# Xbee_Shield_v11.net
KiCad netlist of a schematic drawn in EAGLE
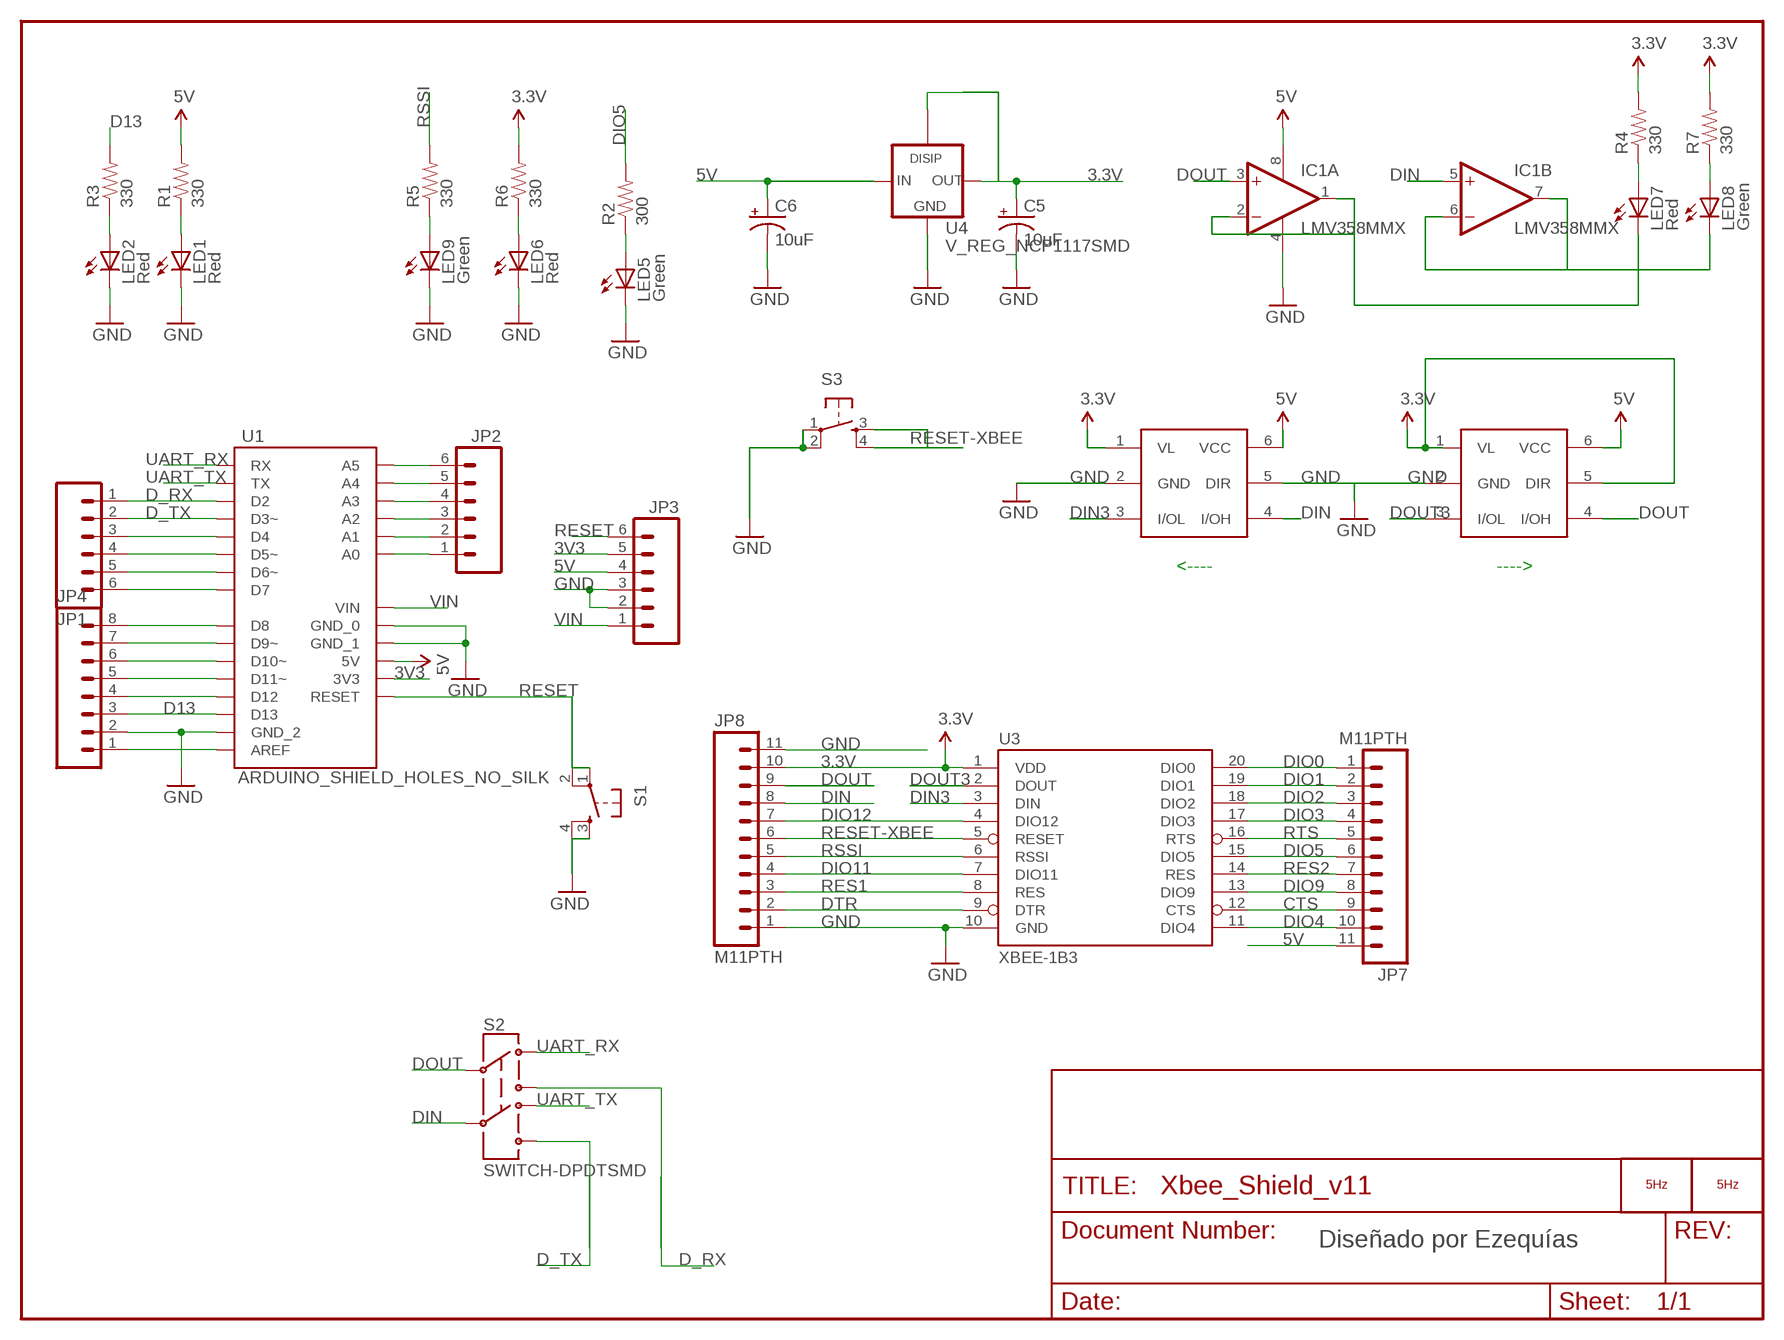
[diagram p0: schematic, sheet 1]

(export (version "E")
  (design (tool "Eeschema 10.0.6"))
  (components
    (comp (ref "C5")
      (value "10uF")
      (footprint "eagle-import:EIA3216")
      (libsource (lib "eagle-import") (part "CAP_POL1206"))
    )
    (comp (ref "C6")
      (value "10uF")
      (footprint "eagle-import:EIA3216")
      (libsource (lib "eagle-import") (part "CAP_POL1206"))
    )
    (comp (ref "IC1")
      (value "LMV358MMX")
      (footprint "eagle-import:MSOP08")
      (libsource (lib "eagle-import") (part "LMV358?MMX"))
    )
    (comp (ref "JP1")
      (value "M06SIP")
      (footprint "eagle-import:1X06")
      (libsource (lib "eagle-import") (part "M06SIP"))
    )
    (comp (ref "JP2")
      (value "M06SIP")
      (footprint "eagle-import:1X06")
      (libsource (lib "eagle-import") (part "M06SIP"))
    )
    (comp (ref "JP3")
      (value "M06SIP")
      (footprint "eagle-import:1X06")
      (libsource (lib "eagle-import") (part "M06SIP"))
    )
    (comp (ref "JP4")
      (value "M081X08")
      (footprint "eagle-import:1X08")
      (libsource (lib "eagle-import") (part "M081X08"))
    )
    (comp (ref "JP7")
      (value "M11PTH")
      (footprint "eagle-import:1X11")
      (libsource (lib "eagle-import") (part "M11PTH"))
    )
    (comp (ref "JP8")
      (value "M11PTH")
      (footprint "eagle-import:1X11")
      (libsource (lib "eagle-import") (part "M11PTH"))
    )
    (comp (ref "LED1")
      (value "Red")
      (footprint "eagle-import:LED-0603")
      (libsource (lib "eagle-import") (part "LED0603"))
    )
    (comp (ref "LED2")
      (value "Red")
      (footprint "eagle-import:LED-0603")
      (libsource (lib "eagle-import") (part "LED0603"))
    )
    (comp (ref "LED5")
      (value "Green")
      (footprint "eagle-import:LED-0603")
      (libsource (lib "eagle-import") (part "LED0603"))
    )
    (comp (ref "LED6")
      (value "Red")
      (footprint "eagle-import:LED-0603")
      (libsource (lib "eagle-import") (part "LED0603"))
    )
    (comp (ref "LED7")
      (value "Red")
      (footprint "eagle-import:LED-0603")
      (libsource (lib "eagle-import") (part "LED0603"))
    )
    (comp (ref "LED8")
      (value "Green")
      (footprint "eagle-import:LED-0603")
      (libsource (lib "eagle-import") (part "LED0603"))
    )
    (comp (ref "LED9")
      (value "Green")
      (footprint "eagle-import:LED-0603")
      (libsource (lib "eagle-import") (part "LED0603"))
    )
    (comp (ref "LOGO1")
      (value "LOGO_5HZ_H_20MM")
      (footprint "eagle-import:5HZ_LOGO_H_20MM")
      (libsource (lib "eagle-import") (part "LOGO_5HZ_H_20MM"))
    )
    (comp (ref "LOGO2")
      (value "LOGO_5HZ_WEB_COOPER_10MM")
      (footprint "eagle-import:5HZ_WEB_COOPER_10MM")
      (libsource (lib "eagle-import") (part "LOGO_5HZ_WEB_COOPER_10MM"))
    )
    (comp (ref "R1")
      (value "330")
      (footprint "eagle-import:0603-RES")
      (libsource (lib "eagle-import") (part "RESISTOR0603-RES"))
    )
    (comp (ref "R2")
      (value "300")
      (footprint "eagle-import:0603-RES")
      (libsource (lib "eagle-import") (part "RESISTOR0603-RES"))
    )
    (comp (ref "R3")
      (value "330")
      (footprint "eagle-import:0603-RES")
      (libsource (lib "eagle-import") (part "RESISTOR0603-RES"))
    )
    (comp (ref "R4")
      (value "330")
      (footprint "eagle-import:0603-RES")
      (libsource (lib "eagle-import") (part "RESISTOR0603-RES"))
    )
    (comp (ref "R5")
      (value "330")
      (footprint "eagle-import:0603-RES")
      (libsource (lib "eagle-import") (part "RESISTOR0603-RES"))
    )
    (comp (ref "R6")
      (value "330")
      (footprint "eagle-import:0603-RES")
      (libsource (lib "eagle-import") (part "RESISTOR0603-RES"))
    )
    (comp (ref "R7")
      (value "330")
      (footprint "eagle-import:0603-RES")
      (libsource (lib "eagle-import") (part "RESISTOR0603-RES"))
    )
    (comp (ref "S1")
      (value "TAC_SWITCHSMD")
      (footprint "eagle-import:TACTILE_SWITCH_SMD")
      (libsource (lib "eagle-import") (part "TAC_SWITCHSMD"))
    )
    (comp (ref "S2")
      (value "SWITCH-DPDTSMD")
      (footprint "eagle-import:AYZ0202")
      (libsource (lib "eagle-import") (part "SWITCH-DPDTSMD"))
    )
    (comp (ref "S3")
      (value "TAC_SWITCHSMD")
      (footprint "eagle-import:TACTILE_SWITCH_SMD")
      (libsource (lib "eagle-import") (part "TAC_SWITCHSMD"))
    )
    (comp (ref "U$7")
      (value "MAX337")
      (footprint "eagle-import:SOT-363")
      (libsource (lib "eagle-import") (part "MAX337"))
    )
    (comp (ref "U$8")
      (value "MAX337")
      (footprint "eagle-import:SOT-363")
      (libsource (lib "eagle-import") (part "MAX337"))
    )
    (comp (ref "U1")
      (value "ARDUINO_SHIELD_HOLES_NO_SILK")
      (footprint "eagle-import:UNO_SHIELD_HOLES_NO_SILK")
      (libsource (lib "eagle-import") (part "ARDUINO_SHIELD_HOLES_NO_SILK"))
    )
    (comp (ref "U3")
      (value "XBEE-1B3")
      (footprint "eagle-import:XBEE-SMD")
      (libsource (lib "eagle-import") (part "XBEE-1B3"))
    )
    (comp (ref "U4")
      (value "V_REG_NCP1117SMD")
      (footprint "eagle-import:SOT223")
      (libsource (lib "eagle-import") (part "V_REG_NCP1117SMD"))
    )
  )
  (nets
    (net (code "1") (name "/3V3") (class "Default")
      (node (ref "JP3") (pin "5") (pinfunction "5_5") (pintype "passive"))
      (node (ref "U1") (pin "3.3V") (pinfunction "3V3_3.3V") (pintype "bidirectional"))
    )
    (net (code "2") (name "/CTS") (class "Default")
      (node (ref "JP7") (pin "9") (pinfunction "9_9") (pintype "passive"))
      (node (ref "U3") (pin "12") (pinfunction "CTS_12") (pintype "output"))
    )
    (net (code "3") (name "/D13") (class "Default")
      (node (ref "JP4") (pin "3") (pinfunction "3_3") (pintype "passive"))
      (node (ref "R3") (pin "2") (pinfunction "2_2") (pintype "passive"))
      (node (ref "U1") (pin "D13") (pinfunction "D13_D13") (pintype "bidirectional"))
    )
    (net (code "4") (name "/DIN") (class "Default")
      (node (ref "IC1") (pin "5") (pinfunction "+IN_5") (pintype "input"))
      (node (ref "JP8") (pin "8") (pinfunction "8_8") (pintype "passive"))
      (node (ref "S2") (pin "5") (pinfunction "5_5") (pintype "bidirectional"))
      (node (ref "U$7") (pin "4") (pinfunction "I/OH_4") (pintype "bidirectional"))
    )
    (net (code "5") (name "/DIN3") (class "Default")
      (node (ref "U$7") (pin "3") (pinfunction "I/OL_3") (pintype "bidirectional"))
      (node (ref "U3") (pin "3") (pinfunction "DIN_3") (pintype "input"))
    )
    (net (code "6") (name "/DIO0") (class "Default")
      (node (ref "JP7") (pin "1") (pinfunction "1_1") (pintype "passive"))
      (node (ref "U3") (pin "20") (pinfunction "DIO0_20") (pintype "bidirectional"))
    )
    (net (code "7") (name "/DIO1") (class "Default")
      (node (ref "JP7") (pin "2") (pinfunction "2_2") (pintype "passive"))
      (node (ref "U3") (pin "19") (pinfunction "DIO1_19") (pintype "bidirectional"))
    )
    (net (code "8") (name "/DIO2") (class "Default")
      (node (ref "JP7") (pin "3") (pinfunction "3_3") (pintype "passive"))
      (node (ref "U3") (pin "18") (pinfunction "DIO2_18") (pintype "bidirectional"))
    )
    (net (code "9") (name "/DIO3") (class "Default")
      (node (ref "JP7") (pin "4") (pinfunction "4_4") (pintype "passive"))
      (node (ref "U3") (pin "17") (pinfunction "DIO3_17") (pintype "bidirectional"))
    )
    (net (code "10") (name "/DIO4") (class "Default")
      (node (ref "JP7") (pin "10") (pinfunction "10_10") (pintype "passive"))
      (node (ref "U3") (pin "11") (pinfunction "DIO4_11") (pintype "bidirectional"))
    )
    (net (code "11") (name "/DIO5") (class "Default")
      (node (ref "JP7") (pin "6") (pinfunction "6_6") (pintype "passive"))
      (node (ref "R2") (pin "2") (pinfunction "2_2") (pintype "passive"))
      (node (ref "U3") (pin "15") (pinfunction "DIO5_15") (pintype "bidirectional"))
    )
    (net (code "12") (name "/DIO9") (class "Default")
      (node (ref "JP7") (pin "8") (pinfunction "8_8") (pintype "passive"))
      (node (ref "U3") (pin "13") (pinfunction "DIO9_13") (pintype "bidirectional"))
    )
    (net (code "13") (name "/DIO11") (class "Default")
      (node (ref "JP8") (pin "4") (pinfunction "4_4") (pintype "passive"))
      (node (ref "U3") (pin "7") (pinfunction "DIO11_7") (pintype "bidirectional"))
    )
    (net (code "14") (name "/DIO12") (class "Default")
      (node (ref "JP8") (pin "7") (pinfunction "7_7") (pintype "passive"))
      (node (ref "U3") (pin "4") (pinfunction "DIO12_4") (pintype "bidirectional"))
    )
    (net (code "15") (name "/DOUT") (class "Default")
      (node (ref "IC1") (pin "3") (pinfunction "+IN_3") (pintype "input"))
      (node (ref "JP8") (pin "9") (pinfunction "9_9") (pintype "passive"))
      (node (ref "S2") (pin "2") (pinfunction "2_2") (pintype "bidirectional"))
      (node (ref "U$8") (pin "4") (pinfunction "I/OH_4") (pintype "bidirectional"))
    )
    (net (code "16") (name "/DOUT3") (class "Default")
      (node (ref "U$8") (pin "3") (pinfunction "I/OL_3") (pintype "bidirectional"))
      (node (ref "U3") (pin "2") (pinfunction "DOUT_2") (pintype "output"))
    )
    (net (code "17") (name "/DTR") (class "Default")
      (node (ref "JP8") (pin "2") (pinfunction "2_2") (pintype "passive"))
      (node (ref "U3") (pin "9") (pinfunction "DTR_9") (pintype "bidirectional"))
    )
    (net (code "18") (name "/D_RX") (class "Default")
      (node (ref "JP1") (pin "1") (pinfunction "1_1") (pintype "passive"))
      (node (ref "S2") (pin "3") (pinfunction "3_3") (pintype "bidirectional"))
      (node (ref "U1") (pin "D2") (pinfunction "D2_D2") (pintype "bidirectional"))
    )
    (net (code "19") (name "/D_TX") (class "Default")
      (node (ref "JP1") (pin "2") (pinfunction "2_2") (pintype "passive"))
      (node (ref "S2") (pin "6") (pinfunction "6_6") (pintype "bidirectional"))
      (node (ref "U1") (pin "D3") (pinfunction "D3~{}_D3") (pintype "bidirectional"))
    )
    (net (code "20") (name "/RES1") (class "Default")
      (node (ref "JP8") (pin "3") (pinfunction "3_3") (pintype "passive"))
      (node (ref "U3") (pin "8") (pinfunction "RES_8") (pintype "bidirectional"))
    )
    (net (code "21") (name "/RES2") (class "Default")
      (node (ref "JP7") (pin "7") (pinfunction "7_7") (pintype "passive"))
      (node (ref "U3") (pin "14") (pinfunction "RES_14") (pintype "bidirectional"))
    )
    (net (code "22") (name "/RESET") (class "Default")
      (node (ref "JP3") (pin "6") (pinfunction "6_6") (pintype "passive"))
      (node (ref "S1") (pin "1") (pinfunction "1_1") (pintype "passive"))
      (node (ref "S1") (pin "2") (pinfunction "2_2") (pintype "passive"))
      (node (ref "U1") (pin "RES") (pinfunction "RESET_RES") (pintype "bidirectional"))
    )
    (net (code "23") (name "/RESET-XBEE") (class "Default")
      (node (ref "JP8") (pin "6") (pinfunction "6_6") (pintype "passive"))
      (node (ref "S3") (pin "3") (pinfunction "3_3") (pintype "passive"))
      (node (ref "S3") (pin "4") (pinfunction "4_4") (pintype "passive"))
      (node (ref "U3") (pin "5") (pinfunction "RESET_5") (pintype "input"))
    )
    (net (code "24") (name "/RSSI") (class "Default")
      (node (ref "JP8") (pin "5") (pinfunction "5_5") (pintype "passive"))
      (node (ref "R5") (pin "2") (pinfunction "2_2") (pintype "passive"))
      (node (ref "U3") (pin "6") (pinfunction "RSSI_6") (pintype "bidirectional"))
    )
    (net (code "25") (name "/RTS") (class "Default")
      (node (ref "JP7") (pin "5") (pinfunction "5_5") (pintype "passive"))
      (node (ref "U3") (pin "16") (pinfunction "RTS_16") (pintype "input"))
    )
    (net (code "26") (name "/UART_RX") (class "Default")
      (node (ref "S2") (pin "1") (pinfunction "1_1") (pintype "bidirectional"))
      (node (ref "U1") (pin "RX") (pinfunction "RX_RX") (pintype "bidirectional"))
    )
    (net (code "27") (name "/UART_TX") (class "Default")
      (node (ref "S2") (pin "4") (pinfunction "4_4") (pintype "bidirectional"))
      (node (ref "U1") (pin "TX") (pinfunction "TX_TX") (pintype "bidirectional"))
    )
    (net (code "28") (name "/VIN") (class "Default")
      (node (ref "JP3") (pin "1") (pinfunction "1_1") (pintype "passive"))
      (node (ref "U1") (pin "VIN") (pinfunction "VIN_VIN") (pintype "bidirectional"))
    )
    (net (code "29") (name "3.3V") (class "Default")
      (node (ref "C5") (pin "A") (pinfunction "+_A") (pintype "passive"))
      (node (ref "JP8") (pin "10") (pinfunction "10_10") (pintype "passive"))
      (node (ref "R4") (pin "2") (pinfunction "2_2") (pintype "passive"))
      (node (ref "R6") (pin "2") (pinfunction "2_2") (pintype "passive"))
      (node (ref "R7") (pin "2") (pinfunction "2_2") (pintype "passive"))
      (node (ref "U$7") (pin "1") (pinfunction "VL_1") (pintype "bidirectional"))
      (node (ref "U$8") (pin "1") (pinfunction "VL_1") (pintype "bidirectional"))
      (node (ref "U$8") (pin "5") (pinfunction "DIR_5") (pintype "bidirectional"))
      (node (ref "U3") (pin "1") (pinfunction "VDD_1") (pintype "power_in"))
      (node (ref "U4") (pin "2") (pinfunction "OUT_2") (pintype "output"))
      (node (ref "U4") (pin "4") (pinfunction "P$1_4") (pintype "bidirectional"))
    )
    (net (code "30") (name "5V") (class "Default")
      (node (ref "C6") (pin "A") (pinfunction "+_A") (pintype "passive"))
      (node (ref "IC1") (pin "8") (pinfunction "V+_8") (pintype "power_in"))
      (node (ref "JP3") (pin "4") (pinfunction "4_4") (pintype "passive"))
      (node (ref "JP7") (pin "11") (pinfunction "11_11") (pintype "passive"))
      (node (ref "R1") (pin "2") (pinfunction "2_2") (pintype "passive"))
      (node (ref "U$7") (pin "6") (pinfunction "VCC_6") (pintype "bidirectional"))
      (node (ref "U$8") (pin "6") (pinfunction "VCC_6") (pintype "bidirectional"))
      (node (ref "U1") (pin "5V") (pinfunction "5V_5V") (pintype "bidirectional"))
      (node (ref "U4") (pin "3") (pinfunction "IN_3") (pintype "input"))
    )
    (net (code "31") (name "GND") (class "Default")
      (node (ref "C5") (pin "C") (pinfunction "-_C") (pintype "passive"))
      (node (ref "C6") (pin "C") (pinfunction "-_C") (pintype "passive"))
      (node (ref "IC1") (pin "4") (pinfunction "V-_4") (pintype "power_in"))
      (node (ref "JP3") (pin "2") (pinfunction "2_2") (pintype "passive"))
      (node (ref "JP3") (pin "3") (pinfunction "3_3") (pintype "passive"))
      (node (ref "JP4") (pin "2") (pinfunction "2_2") (pintype "passive"))
      (node (ref "JP8") (pin "1") (pinfunction "1_1") (pintype "passive"))
      (node (ref "JP8") (pin "11") (pinfunction "11_11") (pintype "passive"))
      (node (ref "LED1") (pin "C") (pinfunction "C_C") (pintype "passive"))
      (node (ref "LED2") (pin "C") (pinfunction "C_C") (pintype "passive"))
      (node (ref "LED5") (pin "C") (pinfunction "C_C") (pintype "passive"))
      (node (ref "LED6") (pin "C") (pinfunction "C_C") (pintype "passive"))
      (node (ref "LED9") (pin "C") (pinfunction "C_C") (pintype "passive"))
      (node (ref "S1") (pin "3") (pinfunction "3_3") (pintype "passive"))
      (node (ref "S1") (pin "4") (pinfunction "4_4") (pintype "passive"))
      (node (ref "S3") (pin "1") (pinfunction "1_1") (pintype "passive"))
      (node (ref "S3") (pin "2") (pinfunction "2_2") (pintype "passive"))
      (node (ref "U$7") (pin "2") (pinfunction "GND_2") (pintype "bidirectional"))
      (node (ref "U$7") (pin "5") (pinfunction "DIR_5") (pintype "bidirectional"))
      (node (ref "U$8") (pin "2") (pinfunction "GND_2") (pintype "bidirectional"))
      (node (ref "U1") (pin "GND_0") (pinfunction "GND_0_GND_0") (pintype "bidirectional"))
      (node (ref "U1") (pin "GND_1") (pinfunction "GND_1_GND_1") (pintype "bidirectional"))
      (node (ref "U1") (pin "GND_2") (pinfunction "GND_2_GND_2") (pintype "bidirectional"))
      (node (ref "U3") (pin "10") (pinfunction "GND_10") (pintype "power_in"))
      (node (ref "U4") (pin "1") (pinfunction "GND_1") (pintype "input"))
    )
    (net (code "32") (name "Net-(IC1A--IN)") (class "Default")
      (node (ref "IC1") (pin "1") (pinfunction "OUT_1") (pintype "output"))
      (node (ref "IC1") (pin "2") (pinfunction "-IN_2") (pintype "input"))
      (node (ref "LED7") (pin "C") (pinfunction "C_C") (pintype "passive"))
    )
    (net (code "33") (name "Net-(IC1B--IN)") (class "Default")
      (node (ref "IC1") (pin "6") (pinfunction "-IN_6") (pintype "input"))
      (node (ref "IC1") (pin "7") (pinfunction "OUT_7") (pintype "output"))
      (node (ref "LED8") (pin "C") (pinfunction "C_C") (pintype "passive"))
    )
    (net (code "34") (name "Net-(JP1-Pad3)") (class "Default")
      (node (ref "JP1") (pin "3") (pinfunction "3_3") (pintype "passive"))
      (node (ref "U1") (pin "D4") (pinfunction "D4_D4") (pintype "bidirectional"))
    )
    (net (code "35") (name "Net-(JP1-Pad6)") (class "Default")
      (node (ref "JP1") (pin "6") (pinfunction "6_6") (pintype "passive"))
      (node (ref "U1") (pin "D7") (pinfunction "D7_D7") (pintype "bidirectional"))
    )
    (net (code "36") (name "Net-(JP2-Pad1)") (class "Default")
      (node (ref "JP2") (pin "1") (pinfunction "1_1") (pintype "passive"))
      (node (ref "U1") (pin "A0") (pinfunction "A0_A0") (pintype "bidirectional"))
    )
    (net (code "37") (name "Net-(JP2-Pad2)") (class "Default")
      (node (ref "JP2") (pin "2") (pinfunction "2_2") (pintype "passive"))
      (node (ref "U1") (pin "A1") (pinfunction "A1_A1") (pintype "bidirectional"))
    )
    (net (code "38") (name "Net-(JP2-Pad3)") (class "Default")
      (node (ref "JP2") (pin "3") (pinfunction "3_3") (pintype "passive"))
      (node (ref "U1") (pin "A2") (pinfunction "A2_A2") (pintype "bidirectional"))
    )
    (net (code "39") (name "Net-(JP2-Pad4)") (class "Default")
      (node (ref "JP2") (pin "4") (pinfunction "4_4") (pintype "passive"))
      (node (ref "U1") (pin "A3") (pinfunction "A3_A3") (pintype "bidirectional"))
    )
    (net (code "40") (name "Net-(JP2-Pad5)") (class "Default")
      (node (ref "JP2") (pin "5") (pinfunction "5_5") (pintype "passive"))
      (node (ref "U1") (pin "A4") (pinfunction "A4_A4") (pintype "bidirectional"))
    )
    (net (code "41") (name "Net-(JP2-Pad6)") (class "Default")
      (node (ref "JP2") (pin "6") (pinfunction "6_6") (pintype "passive"))
      (node (ref "U1") (pin "A5") (pinfunction "A5_A5") (pintype "bidirectional"))
    )
    (net (code "42") (name "Net-(JP4-Pad1)") (class "Default")
      (node (ref "JP4") (pin "1") (pinfunction "1_1") (pintype "passive"))
      (node (ref "U1") (pin "AREF") (pinfunction "AREF_AREF") (pintype "bidirectional"))
    )
    (net (code "43") (name "Net-(JP4-Pad4)") (class "Default")
      (node (ref "JP4") (pin "4") (pinfunction "4_4") (pintype "passive"))
      (node (ref "U1") (pin "D12") (pinfunction "D12_D12") (pintype "bidirectional"))
    )
    (net (code "44") (name "Net-(JP4-Pad8)") (class "Default")
      (node (ref "JP4") (pin "8") (pinfunction "8_8") (pintype "passive"))
      (node (ref "U1") (pin "D8") (pinfunction "D8_D8") (pintype "bidirectional"))
    )
    (net (code "45") (name "Net-(LED1-PadA)") (class "Default")
      (node (ref "LED1") (pin "A") (pinfunction "A_A") (pintype "passive"))
      (node (ref "R1") (pin "1") (pinfunction "1_1") (pintype "passive"))
    )
    (net (code "46") (name "Net-(LED2-PadA)") (class "Default")
      (node (ref "LED2") (pin "A") (pinfunction "A_A") (pintype "passive"))
      (node (ref "R3") (pin "1") (pinfunction "1_1") (pintype "passive"))
    )
    (net (code "47") (name "Net-(LED5-PadA)") (class "Default")
      (node (ref "LED5") (pin "A") (pinfunction "A_A") (pintype "passive"))
      (node (ref "R2") (pin "1") (pinfunction "1_1") (pintype "passive"))
    )
    (net (code "48") (name "Net-(LED6-PadA)") (class "Default")
      (node (ref "LED6") (pin "A") (pinfunction "A_A") (pintype "passive"))
      (node (ref "R6") (pin "1") (pinfunction "1_1") (pintype "passive"))
    )
    (net (code "49") (name "Net-(LED7-PadA)") (class "Default")
      (node (ref "LED7") (pin "A") (pinfunction "A_A") (pintype "passive"))
      (node (ref "R4") (pin "1") (pinfunction "1_1") (pintype "passive"))
    )
    (net (code "50") (name "Net-(LED8-PadA)") (class "Default")
      (node (ref "LED8") (pin "A") (pinfunction "A_A") (pintype "passive"))
      (node (ref "R7") (pin "1") (pinfunction "1_1") (pintype "passive"))
    )
    (net (code "51") (name "Net-(LED9-PadA)") (class "Default")
      (node (ref "LED9") (pin "A") (pinfunction "A_A") (pintype "passive"))
      (node (ref "R5") (pin "1") (pinfunction "1_1") (pintype "passive"))
    )
    (net (code "52") (name "Net-(U1-D5~{})") (class "Default")
      (node (ref "JP1") (pin "4") (pinfunction "4_4") (pintype "passive"))
      (node (ref "U1") (pin "D5") (pinfunction "D5~{}_D5") (pintype "bidirectional"))
    )
    (net (code "53") (name "Net-(U1-D6~{})") (class "Default")
      (node (ref "JP1") (pin "5") (pinfunction "5_5") (pintype "passive"))
      (node (ref "U1") (pin "D6") (pinfunction "D6~{}_D6") (pintype "bidirectional"))
    )
    (net (code "54") (name "Net-(U1-D9~{})") (class "Default")
      (node (ref "JP4") (pin "7") (pinfunction "7_7") (pintype "passive"))
      (node (ref "U1") (pin "D9") (pinfunction "D9~{}_D9") (pintype "bidirectional"))
    )
    (net (code "55") (name "Net-(U1-D10~{})") (class "Default")
      (node (ref "JP4") (pin "6") (pinfunction "6_6") (pintype "passive"))
      (node (ref "U1") (pin "D10") (pinfunction "D10~{}_D10") (pintype "bidirectional"))
    )
    (net (code "56") (name "Net-(U1-D11~{})") (class "Default")
      (node (ref "JP4") (pin "5") (pinfunction "5_5") (pintype "passive"))
      (node (ref "U1") (pin "D11") (pinfunction "D11~{}_D11") (pintype "bidirectional"))
    )
  )
)
